# weichen-a-6.net
KiCad netlist of a schematic drawn in EAGLE
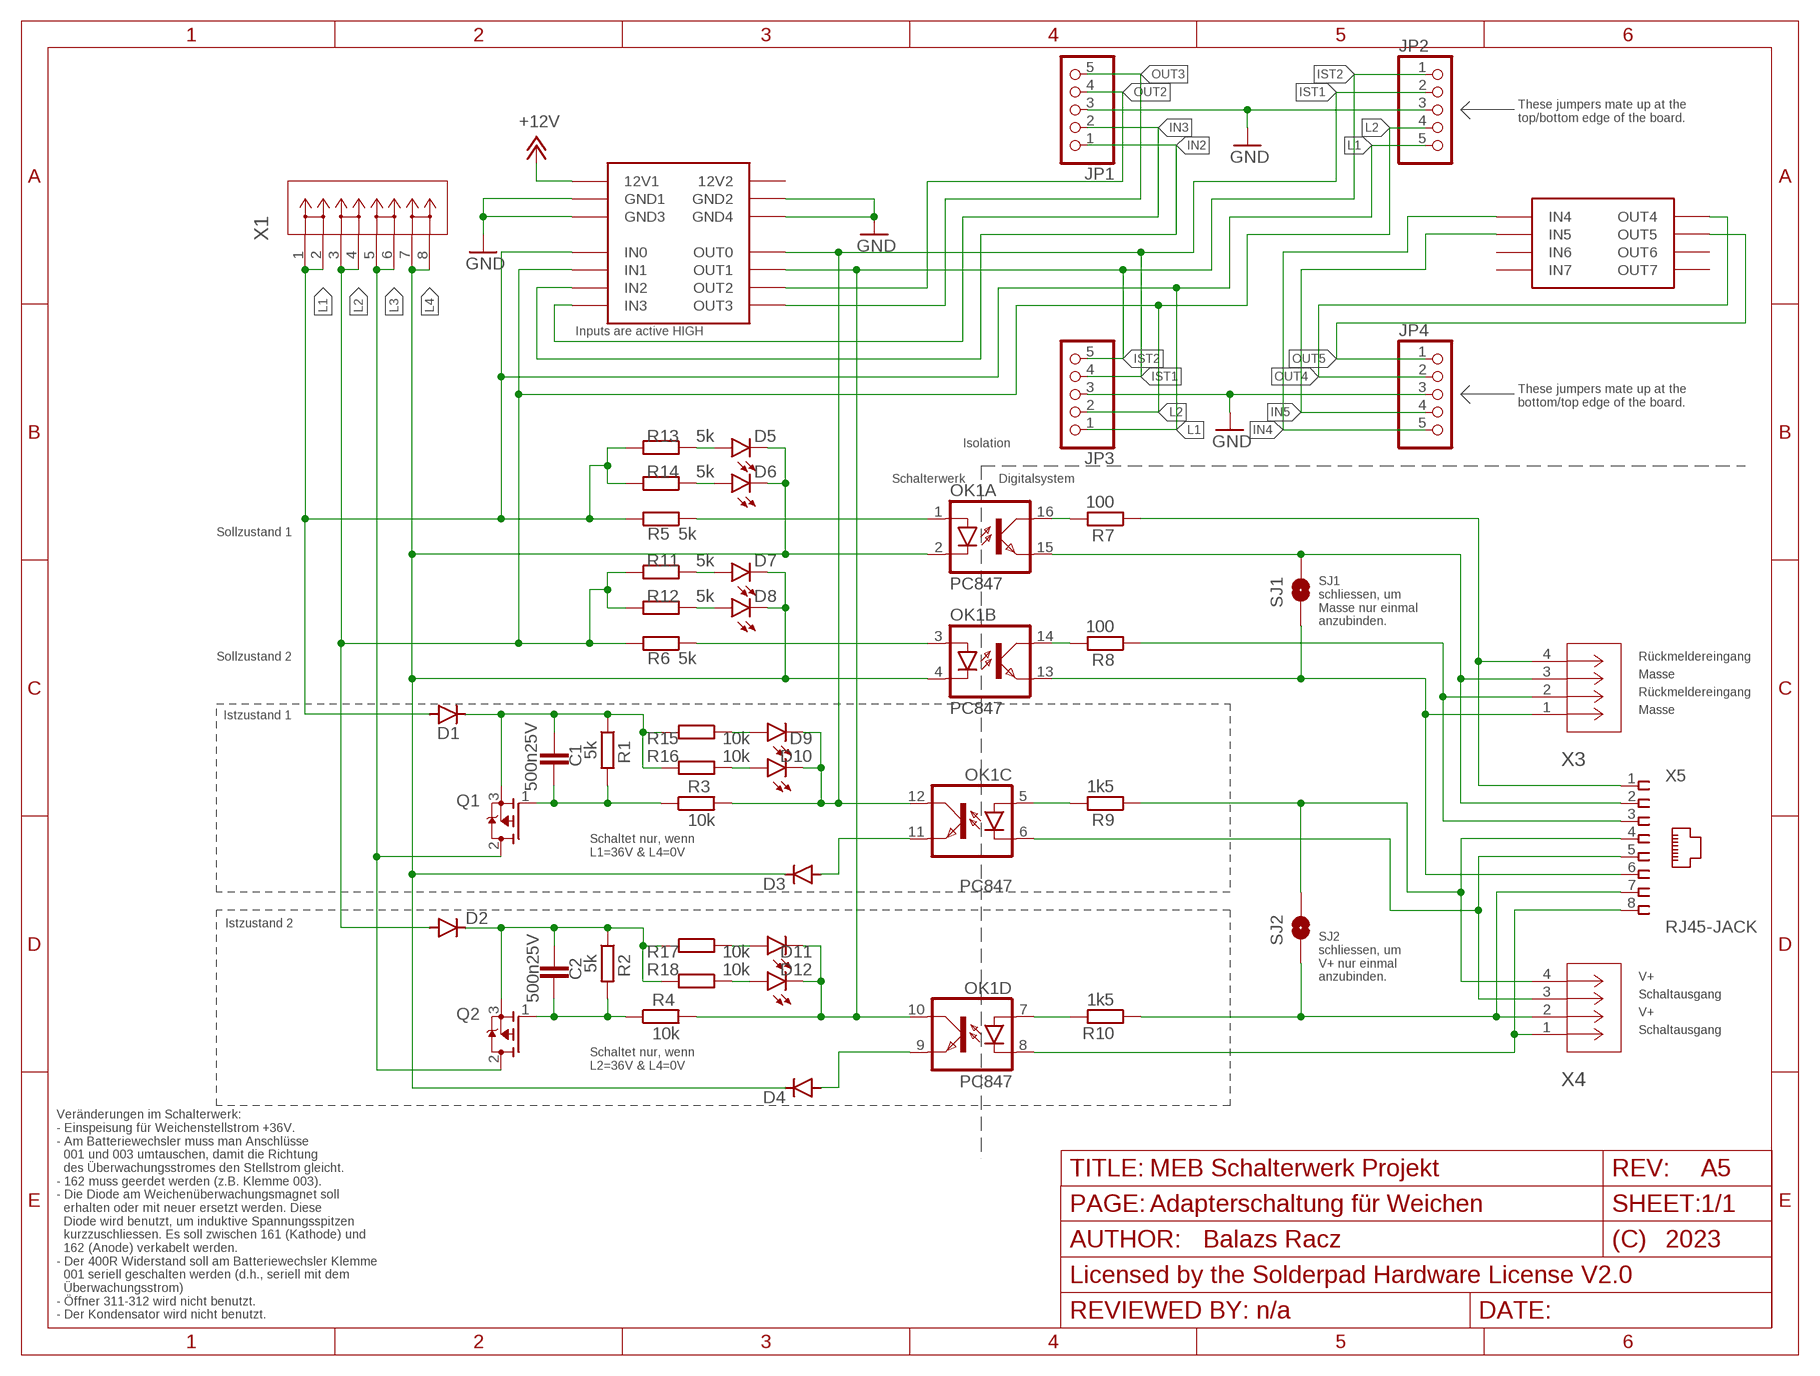
[diagram p0: schematic, sheet 1]

(export (version "E")
  (design (tool "Eeschema 10.0.6"))
  (components
    (comp (ref "C1")
      (value "500n25V")
      (footprint "eagle-import:C0805")
      (libsource (lib "eagle-import") (part "C-EUC0805"))
    )
    (comp (ref "C2")
      (value "500n25V")
      (footprint "eagle-import:C0805")
      (libsource (lib "eagle-import") (part "C-EUC0805"))
    )
    (comp (ref "D1")
      (value "DIODE-DO214AC")
      (footprint "eagle-import:DO214AC")
      (libsource (lib "eagle-import") (part "DIODE-DO214AC"))
    )
    (comp (ref "D2")
      (value "DIODE-DO214AC")
      (footprint "eagle-import:DO214AC")
      (libsource (lib "eagle-import") (part "DIODE-DO214AC"))
    )
    (comp (ref "D3")
      (value "DIODE-MINIMELF")
      (footprint "eagle-import:MINIMELF")
      (libsource (lib "eagle-import") (part "DIODE-MINIMELF"))
    )
    (comp (ref "D4")
      (value "DIODE-MINIMELF")
      (footprint "eagle-import:MINIMELF")
      (libsource (lib "eagle-import") (part "DIODE-MINIMELF"))
    )
    (comp (ref "D5")
      (value "LEDCHIPLED_0603")
      (footprint "eagle-import:CHIPLED_0603")
      (libsource (lib "eagle-import") (part "LEDCHIPLED_0603"))
    )
    (comp (ref "D6")
      (value "LEDHEADER")
      (footprint "eagle-import:LEDHEADER")
      (libsource (lib "eagle-import") (part "LEDHEADER"))
    )
    (comp (ref "D7")
      (value "LEDCHIPLED_0603")
      (footprint "eagle-import:CHIPLED_0603")
      (libsource (lib "eagle-import") (part "LEDCHIPLED_0603"))
    )
    (comp (ref "D8")
      (value "LEDHEADER")
      (footprint "eagle-import:LEDHEADER")
      (libsource (lib "eagle-import") (part "LEDHEADER"))
    )
    (comp (ref "D9")
      (value "LEDCHIPLED_0603")
      (footprint "eagle-import:CHIPLED_0603")
      (libsource (lib "eagle-import") (part "LEDCHIPLED_0603"))
    )
    (comp (ref "D10")
      (value "LEDHEADER")
      (footprint "eagle-import:LEDHEADER")
      (libsource (lib "eagle-import") (part "LEDHEADER"))
    )
    (comp (ref "D11")
      (value "LEDCHIPLED_0603")
      (footprint "eagle-import:CHIPLED_0603")
      (libsource (lib "eagle-import") (part "LEDCHIPLED_0603"))
    )
    (comp (ref "D12")
      (value "LEDHEADER")
      (footprint "eagle-import:LEDHEADER")
      (libsource (lib "eagle-import") (part "LEDHEADER"))
    )
    (comp (ref "JP1")
      (value "PINHD-1X5-EDGE")
      (footprint "eagle-import:1X05")
      (libsource (lib "eagle-import") (part "PINHD-1X5-EDGE"))
    )
    (comp (ref "JP2")
      (value "PINHD-1X5-EDGE")
      (footprint "eagle-import:1X05")
      (libsource (lib "eagle-import") (part "PINHD-1X5-EDGE"))
    )
    (comp (ref "JP3")
      (value "PINHD-1X5-EDGE")
      (footprint "eagle-import:1X05")
      (libsource (lib "eagle-import") (part "PINHD-1X5-EDGE"))
    )
    (comp (ref "JP4")
      (value "PINHD-1X5-EDGE")
      (footprint "eagle-import:1X05")
      (libsource (lib "eagle-import") (part "PINHD-1X5-EDGE"))
    )
    (comp (ref "OK1")
      (value "PC847")
      (footprint "eagle-import:DIL16")
      (libsource (lib "eagle-import") (part "PC847"))
    )
    (comp (ref "Q1")
      (value "P-MOSFET")
      (footprint "eagle-import:DPAK-2")
      (fields (field (name "MANUFACTURER") "Infineon"))
      (libsource (lib "eagle-import") (part "P-MOSFET"))
    )
    (comp (ref "Q2")
      (value "P-MOSFET")
      (footprint "eagle-import:DPAK-2")
      (fields (field (name "MANUFACTURER") "Infineon"))
      (libsource (lib "eagle-import") (part "P-MOSFET"))
    )
    (comp (ref "R1")
      (value "5k")
      (footprint "eagle-import:R0805")
      (libsource (lib "eagle-import") (part "R-EU_R0805"))
    )
    (comp (ref "R2")
      (value "5k")
      (footprint "eagle-import:R0805")
      (libsource (lib "eagle-import") (part "R-EU_R0805"))
    )
    (comp (ref "R3")
      (value "10k")
      (footprint "eagle-import:R0805")
      (libsource (lib "eagle-import") (part "R-EU_R0805"))
    )
    (comp (ref "R4")
      (value "10k")
      (footprint "eagle-import:R0805")
      (libsource (lib "eagle-import") (part "R-EU_R0805"))
    )
    (comp (ref "R5")
      (value "5k")
      (footprint "eagle-import:R0805")
      (libsource (lib "eagle-import") (part "R-EU_R0805"))
    )
    (comp (ref "R6")
      (value "5k")
      (footprint "eagle-import:R0805")
      (libsource (lib "eagle-import") (part "R-EU_R0805"))
    )
    (comp (ref "R7")
      (value "100")
      (footprint "eagle-import:R0805")
      (libsource (lib "eagle-import") (part "R-EU_R0805"))
    )
    (comp (ref "R8")
      (value "100")
      (footprint "eagle-import:R0805")
      (libsource (lib "eagle-import") (part "R-EU_R0805"))
    )
    (comp (ref "R9")
      (value "1k5")
      (footprint "eagle-import:R0805")
      (libsource (lib "eagle-import") (part "R-EU_R0805"))
    )
    (comp (ref "R10")
      (value "1k5")
      (footprint "eagle-import:R0805")
      (libsource (lib "eagle-import") (part "R-EU_R0805"))
    )
    (comp (ref "R11")
      (value "5k")
      (footprint "eagle-import:R0805")
      (libsource (lib "eagle-import") (part "R-EU_R0805"))
    )
    (comp (ref "R12")
      (value "5k")
      (footprint "eagle-import:R0805")
      (libsource (lib "eagle-import") (part "R-EU_R0805"))
    )
    (comp (ref "R13")
      (value "5k")
      (footprint "eagle-import:R0805")
      (libsource (lib "eagle-import") (part "R-EU_R0805"))
    )
    (comp (ref "R14")
      (value "5k")
      (footprint "eagle-import:R0805")
      (libsource (lib "eagle-import") (part "R-EU_R0805"))
    )
    (comp (ref "R15")
      (value "10k")
      (footprint "eagle-import:R0805")
      (libsource (lib "eagle-import") (part "R-EU_R0805"))
    )
    (comp (ref "R16")
      (value "10k")
      (footprint "eagle-import:R0805")
      (libsource (lib "eagle-import") (part "R-EU_R0805"))
    )
    (comp (ref "R17")
      (value "10k")
      (footprint "eagle-import:R0805")
      (libsource (lib "eagle-import") (part "R-EU_R0805"))
    )
    (comp (ref "R18")
      (value "10k")
      (footprint "eagle-import:R0805")
      (libsource (lib "eagle-import") (part "R-EU_R0805"))
    )
    (comp (ref "SJ1")
      (value "SJRND2")
      (footprint "eagle-import:SJ_RND2")
      (libsource (lib "eagle-import") (part "SJRND2"))
    )
    (comp (ref "SJ2")
      (value "SJRND2")
      (footprint "eagle-import:SJ_RND2")
      (libsource (lib "eagle-import") (part "SJRND2"))
    )
    (comp (ref "X1")
      (value "PHNX_4P_508CONN_1017493")
      (footprint "eagle-import:PHNX_4P_508")
      (fields
        (field (name "MANUFACTURER_PART_NUMBER") "1017505")
        (field (name "COPYRIGHT") "Copyright (C) 2023 Ultra Librarian. All rights reserved.")
      )
      (libsource (lib "eagle-import") (part "PHNX_4P_508CONN_1017493"))
    )
    (comp (ref "X2")
      (value "IO-HAT")
      (footprint "eagle-import:IOBOARD")
      (libsource (lib "eagle-import") (part "IO-HAT"))
    )
    (comp (ref "X3")
      (value "PHNX_4P_350CONN_1984989_PXC")
      (footprint "eagle-import:PHNX_4P_350")
      (fields
        (field (name "MANUFACTURER_PART_NUMBER") "1984989")
        (field (name "COPYRIGHT") "Copyright (C) 2023 Ultra Librarian. All rights reserved.")
      )
      (libsource (lib "eagle-import") (part "PHNX_4P_350CONN_1984989_PXC"))
    )
    (comp (ref "X4")
      (value "PHNX_4P_350CONN_1984989_PXC")
      (footprint "eagle-import:PHNX_4P_350")
      (fields
        (field (name "MANUFACTURER_PART_NUMBER") "1984989")
        (field (name "COPYRIGHT") "Copyright (C) 2023 Ultra Librarian. All rights reserved.")
      )
      (libsource (lib "eagle-import") (part "PHNX_4P_350CONN_1984989_PXC"))
    )
    (comp (ref "X5")
      (value "RJ45-JACK")
      (footprint "eagle-import:RJ45-PULSE-E5J88")
      (libsource (lib "eagle-import") (part "RJ45-JACKRJ45-PULSE-E5J00"))
    )
  )
  (nets
    (net (code "1") (name "+12V") (class "Default")
      (node (ref "X2") (pin "P$1") (pinfunction "12V1_P$1") (pintype "power_in"))
    )
    (net (code "2") (name "/12V2") (class "Default")
      (node (ref "X2") (pin "P$22") (pinfunction "12V2_P$22") (pintype "power_in"))
    )
    (net (code "3") (name "GND") (class "Default")
      (node (ref "JP1") (pin "3") (pinfunction "3_3") (pintype "passive"))
      (node (ref "JP2") (pin "3") (pinfunction "3_3") (pintype "passive"))
      (node (ref "JP3") (pin "3") (pinfunction "3_3") (pintype "passive"))
      (node (ref "JP4") (pin "3") (pinfunction "3_3") (pintype "passive"))
      (node (ref "X2") (pin "P$11") (pinfunction "GND3_P$11") (pintype "power_in"))
      (node (ref "X2") (pin "P$12") (pinfunction "GND4_P$12") (pintype "power_in"))
      (node (ref "X2") (pin "P$2") (pinfunction "GND1_P$2") (pintype "power_in"))
      (node (ref "X2") (pin "P$21") (pinfunction "GND2_P$21") (pintype "power_in"))
    )
    (net (code "4") (name "IN2") (class "Default")
      (node (ref "JP1") (pin "1") (pinfunction "1_1") (pintype "passive"))
      (node (ref "X2") (pin "P$5") (pinfunction "IN2_P$5") (pintype "input"))
    )
    (net (code "5") (name "IN3") (class "Default")
      (node (ref "JP1") (pin "2") (pinfunction "2_2") (pintype "passive"))
      (node (ref "X2") (pin "P$6") (pinfunction "IN3_P$6") (pintype "input"))
    )
    (net (code "6") (name "IN4") (class "Default")
      (node (ref "JP4") (pin "5") (pinfunction "5_5") (pintype "passive"))
      (node (ref "X2") (pin "P$7") (pinfunction "IN4_P$7") (pintype "input"))
    )
    (net (code "7") (name "IN5") (class "Default")
      (node (ref "JP4") (pin "4") (pinfunction "4_4") (pintype "passive"))
      (node (ref "X2") (pin "P$8") (pinfunction "IN5_P$8") (pintype "input"))
    )
    (net (code "8") (name "IST1") (class "Default")
      (node (ref "D10") (pin "C") (pinfunction "C_C") (pintype "passive"))
      (node (ref "D9") (pin "C") (pinfunction "C_C") (pintype "passive"))
      (node (ref "JP2") (pin "2") (pinfunction "2_2") (pintype "passive"))
      (node (ref "JP3") (pin "4") (pinfunction "4_4") (pintype "passive"))
      (node (ref "OK1") (pin "12") (pinfunction "COL_12") (pintype "passive"))
      (node (ref "R3") (pin "2") (pinfunction "2_2") (pintype "passive"))
      (node (ref "X2") (pin "P$20") (pinfunction "OUT0_P$20") (pintype "open_collector"))
    )
    (net (code "9") (name "IST2") (class "Default")
      (node (ref "D11") (pin "C") (pinfunction "C_C") (pintype "passive"))
      (node (ref "D12") (pin "C") (pinfunction "C_C") (pintype "passive"))
      (node (ref "JP2") (pin "1") (pinfunction "1_1") (pintype "passive"))
      (node (ref "JP3") (pin "5") (pinfunction "5_5") (pintype "passive"))
      (node (ref "OK1") (pin "10") (pinfunction "COL_10") (pintype "passive"))
      (node (ref "R4") (pin "2") (pinfunction "2_2") (pintype "passive"))
      (node (ref "X2") (pin "P$19") (pinfunction "OUT1_P$19") (pintype "open_collector"))
    )
    (net (code "10") (name "L1") (class "Default")
      (node (ref "D1") (pin "A") (pinfunction "A_A") (pintype "passive"))
      (node (ref "JP2") (pin "5") (pinfunction "5_5") (pintype "passive"))
      (node (ref "JP3") (pin "1") (pinfunction "1_1") (pintype "passive"))
      (node (ref "R13") (pin "2") (pinfunction "2_2") (pintype "passive"))
      (node (ref "R14") (pin "2") (pinfunction "2_2") (pintype "passive"))
      (node (ref "R5") (pin "2") (pinfunction "2_2") (pintype "passive"))
      (node (ref "X1") (pin "1") (pinfunction "1_1") (pintype "passive"))
      (node (ref "X1") (pin "2") (pinfunction "2_2") (pintype "passive"))
      (node (ref "X2") (pin "P$3") (pinfunction "IN0_P$3") (pintype "input"))
    )
    (net (code "11") (name "L2") (class "Default")
      (node (ref "D2") (pin "A") (pinfunction "A_A") (pintype "passive"))
      (node (ref "JP2") (pin "4") (pinfunction "4_4") (pintype "passive"))
      (node (ref "JP3") (pin "2") (pinfunction "2_2") (pintype "passive"))
      (node (ref "R11") (pin "2") (pinfunction "2_2") (pintype "passive"))
      (node (ref "R12") (pin "2") (pinfunction "2_2") (pintype "passive"))
      (node (ref "R6") (pin "2") (pinfunction "2_2") (pintype "passive"))
      (node (ref "X1") (pin "3") (pinfunction "3_3") (pintype "passive"))
      (node (ref "X1") (pin "4") (pinfunction "4_4") (pintype "passive"))
      (node (ref "X2") (pin "P$4") (pinfunction "IN1_P$4") (pintype "input"))
    )
    (net (code "12") (name "L3") (class "Default")
      (node (ref "Q1") (pin "2") (pinfunction "D_2") (pintype "passive"))
      (node (ref "Q2") (pin "2") (pinfunction "D_2") (pintype "passive"))
      (node (ref "X1") (pin "5") (pinfunction "5_5") (pintype "passive"))
      (node (ref "X1") (pin "6") (pinfunction "6_6") (pintype "passive"))
    )
    (net (code "13") (name "L4") (class "Default")
      (node (ref "D3") (pin "C") (pinfunction "C_C") (pintype "passive"))
      (node (ref "D4") (pin "C") (pinfunction "C_C") (pintype "passive"))
      (node (ref "D5") (pin "C") (pinfunction "C_C") (pintype "passive"))
      (node (ref "D6") (pin "C") (pinfunction "C_C") (pintype "passive"))
      (node (ref "D7") (pin "C") (pinfunction "C_C") (pintype "passive"))
      (node (ref "D8") (pin "C") (pinfunction "C_C") (pintype "passive"))
      (node (ref "OK1") (pin "2") (pinfunction "C_2") (pintype "passive"))
      (node (ref "OK1") (pin "4") (pinfunction "C_4") (pintype "passive"))
      (node (ref "X1") (pin "7") (pinfunction "7_7") (pintype "passive"))
      (node (ref "X1") (pin "8") (pinfunction "8_8") (pintype "passive"))
    )
    (net (code "14") (name "Net-(D5-PadA)") (class "Default")
      (node (ref "D5") (pin "A") (pinfunction "A_A") (pintype "passive"))
      (node (ref "R13") (pin "1") (pinfunction "1_1") (pintype "passive"))
    )
    (net (code "15") (name "Net-(D6-PadA)") (class "Default")
      (node (ref "D6") (pin "A") (pinfunction "A_A") (pintype "passive"))
      (node (ref "R14") (pin "1") (pinfunction "1_1") (pintype "passive"))
    )
    (net (code "16") (name "Net-(D7-PadA)") (class "Default")
      (node (ref "D7") (pin "A") (pinfunction "A_A") (pintype "passive"))
      (node (ref "R11") (pin "1") (pinfunction "1_1") (pintype "passive"))
    )
    (net (code "17") (name "Net-(D8-PadA)") (class "Default")
      (node (ref "D8") (pin "A") (pinfunction "A_A") (pintype "passive"))
      (node (ref "R12") (pin "1") (pinfunction "1_1") (pintype "passive"))
    )
    (net (code "18") (name "Net-(D9-PadA)") (class "Default")
      (node (ref "D9") (pin "A") (pinfunction "A_A") (pintype "passive"))
      (node (ref "R15") (pin "1") (pinfunction "1_1") (pintype "passive"))
    )
    (net (code "19") (name "Net-(D10-PadA)") (class "Default")
      (node (ref "D10") (pin "A") (pinfunction "A_A") (pintype "passive"))
      (node (ref "R16") (pin "1") (pinfunction "1_1") (pintype "passive"))
    )
    (net (code "20") (name "Net-(D11-PadA)") (class "Default")
      (node (ref "D11") (pin "A") (pinfunction "A_A") (pintype "passive"))
      (node (ref "R17") (pin "1") (pinfunction "1_1") (pintype "passive"))
    )
    (net (code "21") (name "Net-(D12-PadA)") (class "Default")
      (node (ref "D12") (pin "A") (pinfunction "A_A") (pintype "passive"))
      (node (ref "R18") (pin "1") (pinfunction "1_1") (pintype "passive"))
    )
    (net (code "22") (name "Net-(OK1A-A)") (class "Default")
      (node (ref "OK1") (pin "1") (pinfunction "A_1") (pintype "passive"))
      (node (ref "R5") (pin "1") (pinfunction "1_1") (pintype "passive"))
    )
    (net (code "23") (name "Net-(OK1A-COL)") (class "Default")
      (node (ref "OK1") (pin "16") (pinfunction "COL_16") (pintype "passive"))
      (node (ref "R7") (pin "2") (pinfunction "2_2") (pintype "passive"))
    )
    (net (code "24") (name "Net-(OK1A-EMIT)") (class "Default")
      (node (ref "OK1") (pin "15") (pinfunction "EMIT_15") (pintype "passive"))
      (node (ref "SJ1") (pin "P$2") (pinfunction "2_P$2") (pintype "passive"))
      (node (ref "X3") (pin "3") (pinfunction "3_3") (pintype "passive"))
      (node (ref "X5") (pin "2") (pinfunction "2_2") (pintype "passive"))
    )
    (net (code "25") (name "Net-(OK1B-A)") (class "Default")
      (node (ref "OK1") (pin "3") (pinfunction "A_3") (pintype "passive"))
      (node (ref "R6") (pin "1") (pinfunction "1_1") (pintype "passive"))
    )
    (net (code "26") (name "Net-(OK1B-COL)") (class "Default")
      (node (ref "OK1") (pin "14") (pinfunction "COL_14") (pintype "passive"))
      (node (ref "R8") (pin "2") (pinfunction "2_2") (pintype "passive"))
    )
    (net (code "27") (name "Net-(OK1B-EMIT)") (class "Default")
      (node (ref "OK1") (pin "13") (pinfunction "EMIT_13") (pintype "passive"))
      (node (ref "SJ1") (pin "P$1") (pinfunction "1_P$1") (pintype "passive"))
      (node (ref "X3") (pin "1") (pinfunction "1_1") (pintype "passive"))
      (node (ref "X5") (pin "6") (pinfunction "6_6") (pintype "passive"))
    )
    (net (code "28") (name "Net-(OK1C-A)") (class "Default")
      (node (ref "OK1") (pin "5") (pinfunction "A_5") (pintype "passive"))
      (node (ref "R9") (pin "2") (pinfunction "2_2") (pintype "passive"))
    )
    (net (code "29") (name "Net-(OK1C-C)") (class "Default")
      (node (ref "OK1") (pin "6") (pinfunction "C_6") (pintype "passive"))
      (node (ref "X4") (pin "3") (pinfunction "3_3") (pintype "passive"))
      (node (ref "X5") (pin "5") (pinfunction "5_5") (pintype "passive"))
    )
    (net (code "30") (name "Net-(OK1C-EMIT)") (class "Default")
      (node (ref "D3") (pin "A") (pinfunction "A_A") (pintype "passive"))
      (node (ref "OK1") (pin "11") (pinfunction "EMIT_11") (pintype "passive"))
    )
    (net (code "31") (name "Net-(OK1D-A)") (class "Default")
      (node (ref "OK1") (pin "7") (pinfunction "A_7") (pintype "passive"))
      (node (ref "R10") (pin "2") (pinfunction "2_2") (pintype "passive"))
    )
    (net (code "32") (name "Net-(OK1D-C)") (class "Default")
      (node (ref "OK1") (pin "8") (pinfunction "C_8") (pintype "passive"))
      (node (ref "X4") (pin "1") (pinfunction "1_1") (pintype "passive"))
      (node (ref "X5") (pin "8") (pinfunction "8_8") (pintype "passive"))
    )
    (net (code "33") (name "Net-(OK1D-EMIT)") (class "Default")
      (node (ref "D4") (pin "A") (pinfunction "A_A") (pintype "passive"))
      (node (ref "OK1") (pin "9") (pinfunction "EMIT_9") (pintype "passive"))
    )
    (net (code "34") (name "Net-(Q1-G)") (class "Default")
      (node (ref "C1") (pin "2") (pinfunction "2_2") (pintype "passive"))
      (node (ref "Q1") (pin "1") (pinfunction "G_1") (pintype "passive"))
      (node (ref "R1") (pin "2") (pinfunction "2_2") (pintype "passive"))
      (node (ref "R3") (pin "1") (pinfunction "1_1") (pintype "passive"))
    )
    (net (code "35") (name "Net-(Q1-S)") (class "Default")
      (node (ref "C1") (pin "1") (pinfunction "1_1") (pintype "passive"))
      (node (ref "D1") (pin "C") (pinfunction "C_C") (pintype "passive"))
      (node (ref "Q1") (pin "3") (pinfunction "S_3") (pintype "passive"))
      (node (ref "R1") (pin "1") (pinfunction "1_1") (pintype "passive"))
      (node (ref "R15") (pin "2") (pinfunction "2_2") (pintype "passive"))
      (node (ref "R16") (pin "2") (pinfunction "2_2") (pintype "passive"))
    )
    (net (code "36") (name "Net-(Q2-G)") (class "Default")
      (node (ref "C2") (pin "2") (pinfunction "2_2") (pintype "passive"))
      (node (ref "Q2") (pin "1") (pinfunction "G_1") (pintype "passive"))
      (node (ref "R2") (pin "2") (pinfunction "2_2") (pintype "passive"))
      (node (ref "R4") (pin "1") (pinfunction "1_1") (pintype "passive"))
    )
    (net (code "37") (name "Net-(Q2-S)") (class "Default")
      (node (ref "C2") (pin "1") (pinfunction "1_1") (pintype "passive"))
      (node (ref "D2") (pin "C") (pinfunction "C_C") (pintype "passive"))
      (node (ref "Q2") (pin "3") (pinfunction "S_3") (pintype "passive"))
      (node (ref "R17") (pin "2") (pinfunction "2_2") (pintype "passive"))
      (node (ref "R18") (pin "2") (pinfunction "2_2") (pintype "passive"))
      (node (ref "R2") (pin "1") (pinfunction "1_1") (pintype "passive"))
    )
    (net (code "38") (name "Net-(R7-Pad1)") (class "Default")
      (node (ref "R7") (pin "1") (pinfunction "1_1") (pintype "passive"))
      (node (ref "X3") (pin "4") (pinfunction "4_4") (pintype "passive"))
      (node (ref "X5") (pin "1") (pinfunction "1_1") (pintype "passive"))
    )
    (net (code "39") (name "Net-(R8-Pad1)") (class "Default")
      (node (ref "R8") (pin "1") (pinfunction "1_1") (pintype "passive"))
      (node (ref "X3") (pin "2") (pinfunction "2_2") (pintype "passive"))
      (node (ref "X5") (pin "3") (pinfunction "3_3") (pintype "passive"))
    )
    (net (code "40") (name "Net-(SJ2-1)") (class "Default")
      (node (ref "R10") (pin "1") (pinfunction "1_1") (pintype "passive"))
      (node (ref "SJ2") (pin "P$1") (pinfunction "1_P$1") (pintype "passive"))
      (node (ref "X4") (pin "2") (pinfunction "2_2") (pintype "passive"))
      (node (ref "X5") (pin "7") (pinfunction "7_7") (pintype "passive"))
    )
    (net (code "41") (name "Net-(SJ2-2)") (class "Default")
      (node (ref "R9") (pin "1") (pinfunction "1_1") (pintype "passive"))
      (node (ref "SJ2") (pin "P$2") (pinfunction "2_P$2") (pintype "passive"))
      (node (ref "X4") (pin "4") (pinfunction "4_4") (pintype "passive"))
      (node (ref "X5") (pin "4") (pinfunction "4_4") (pintype "passive"))
    )
    (net (code "42") (name "OUT2") (class "Default")
      (node (ref "JP1") (pin "4") (pinfunction "4_4") (pintype "passive"))
      (node (ref "X2") (pin "P$18") (pinfunction "OUT2_P$18") (pintype "open_collector"))
    )
    (net (code "43") (name "OUT3") (class "Default")
      (node (ref "JP1") (pin "5") (pinfunction "5_5") (pintype "passive"))
      (node (ref "X2") (pin "P$17") (pinfunction "OUT3_P$17") (pintype "open_collector"))
    )
    (net (code "44") (name "OUT4") (class "Default")
      (node (ref "JP4") (pin "2") (pinfunction "2_2") (pintype "passive"))
      (node (ref "X2") (pin "P$16") (pinfunction "OUT4_P$16") (pintype "open_collector"))
    )
    (net (code "45") (name "OUT5") (class "Default")
      (node (ref "JP4") (pin "1") (pinfunction "1_1") (pintype "passive"))
      (node (ref "X2") (pin "P$15") (pinfunction "OUT5_P$15") (pintype "open_collector"))
    )
    (net (code "46") (name "unconnected-(X2B-IN6-PadP$9)") (class "Default")
      (node (ref "X2") (pin "P$9") (pinfunction "IN6_P$9") (pintype "input"))
    )
    (net (code "47") (name "unconnected-(X2B-IN7-PadP$10)") (class "Default")
      (node (ref "X2") (pin "P$10") (pinfunction "IN7_P$10") (pintype "input"))
    )
    (net (code "48") (name "unconnected-(X2B-OUT6-PadP$14)") (class "Default")
      (node (ref "X2") (pin "P$14") (pinfunction "OUT6_P$14") (pintype "open_collector"))
    )
    (net (code "49") (name "unconnected-(X2B-OUT7-PadP$13)") (class "Default")
      (node (ref "X2") (pin "P$13") (pinfunction "OUT7_P$13") (pintype "open_collector"))
    )
  )
)
